# 01_2019_-_PLACA_LEDS_V1.net
KiCad netlist of a schematic drawn in EAGLE
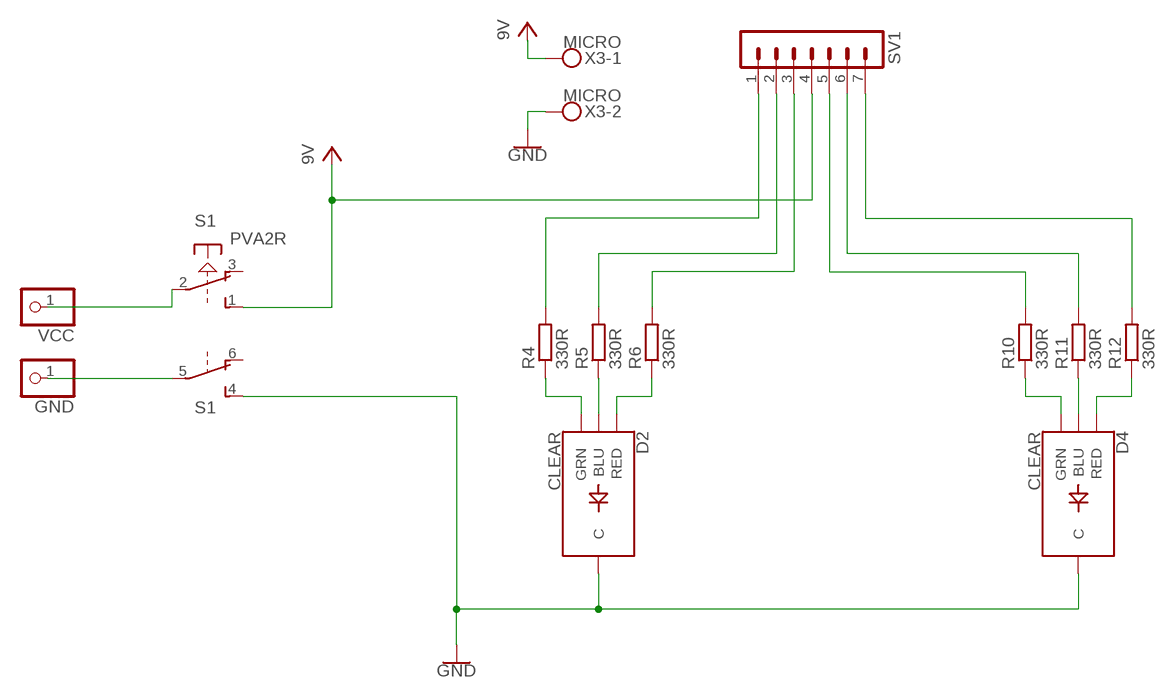
[diagram p0: schematic, sheet 1]

(export (version "E")
  (design (tool "Eeschema 10.0.6"))
  (components
    (comp (ref "D2")
      (value "CLEAR")
      (footprint "eagle-import:LED-RGB-THRU")
      (libsource (lib "eagle-import") (part "LED-RGB-CCCLEAR"))
    )
    (comp (ref "D4")
      (value "CLEAR")
      (footprint "eagle-import:LED-RGB-THRU")
      (libsource (lib "eagle-import") (part "LED-RGB-CCCLEAR"))
    )
    (comp (ref "GND")
      (value "PINHD-1X1")
      (footprint "eagle-import:1X01")
      (libsource (lib "eagle-import") (part "PINHD-1X1"))
    )
    (comp (ref "R4")
      (value "330R")
      (footprint "eagle-import:0204_7")
      (libsource (lib "eagle-import") (part "R-EU_0204/7"))
    )
    (comp (ref "R5")
      (value "330R")
      (footprint "eagle-import:0204_7")
      (libsource (lib "eagle-import") (part "R-EU_0204/7"))
    )
    (comp (ref "R6")
      (value "330R")
      (footprint "eagle-import:0204_7")
      (libsource (lib "eagle-import") (part "R-EU_0204/7"))
    )
    (comp (ref "R10")
      (value "330R")
      (footprint "eagle-import:0204_7")
      (libsource (lib "eagle-import") (part "R-EU_0204/7"))
    )
    (comp (ref "R11")
      (value "330R")
      (footprint "eagle-import:0204_7")
      (libsource (lib "eagle-import") (part "R-EU_0204/7"))
    )
    (comp (ref "R12")
      (value "330R")
      (footprint "eagle-import:0204_7")
      (libsource (lib "eagle-import") (part "R-EU_0204/7"))
    )
    (comp (ref "S1")
      (value "PVA2R")
      (footprint "eagle-import:PVA2R")
      (libsource (lib "eagle-import") (part "PVA2R"))
    )
    (comp (ref "SV1")
      (value "MA07-1")
      (footprint "eagle-import:MA07-1")
      (libsource (lib "eagle-import") (part "MA07-1"))
    )
    (comp (ref "VCC")
      (value "PINHD-1X1")
      (footprint "eagle-import:1X01")
      (libsource (lib "eagle-import") (part "PINHD-1X1"))
    )
    (comp (ref "X3")
      (value "MICRO")
      (footprint "eagle-import:MKDSN1,5_2-5,08")
      (libsource (lib "eagle-import") (part "MKDSN1,5/2-5,08"))
    )
  )
  (nets
    (net (code "1") (name "9V") (class "Default")
      (node (ref "S1") (pin "1") (pinfunction "S_1") (pintype "passive"))
      (node (ref "SV1") (pin "4") (pinfunction "4_4") (pintype "passive"))
      (node (ref "X3") (pin "1") (pinfunction "KL_1") (pintype "passive"))
    )
    (net (code "2") (name "GND") (class "Default")
      (node (ref "D2") (pin "2") (pinfunction "C_2") (pintype "bidirectional"))
      (node (ref "D4") (pin "2") (pinfunction "C_2") (pintype "bidirectional"))
      (node (ref "S1") (pin "4") (pinfunction "S_4") (pintype "passive"))
      (node (ref "X3") (pin "2") (pinfunction "KL_2") (pintype "passive"))
    )
    (net (code "3") (name "Net-(D2-BLU)") (class "Default")
      (node (ref "D2") (pin "4") (pinfunction "BLU_4") (pintype "bidirectional"))
      (node (ref "R5") (pin "1") (pinfunction "1_1") (pintype "passive"))
    )
    (net (code "4") (name "Net-(D2-GRN)") (class "Default")
      (node (ref "D2") (pin "3") (pinfunction "GRN_3") (pintype "bidirectional"))
      (node (ref "R4") (pin "1") (pinfunction "1_1") (pintype "passive"))
    )
    (net (code "5") (name "Net-(D2-RED)") (class "Default")
      (node (ref "D2") (pin "1") (pinfunction "RED_1") (pintype "bidirectional"))
      (node (ref "R6") (pin "1") (pinfunction "1_1") (pintype "passive"))
    )
    (net (code "6") (name "Net-(D4-BLU)") (class "Default")
      (node (ref "D4") (pin "4") (pinfunction "BLU_4") (pintype "bidirectional"))
      (node (ref "R11") (pin "1") (pinfunction "1_1") (pintype "passive"))
    )
    (net (code "7") (name "Net-(D4-GRN)") (class "Default")
      (node (ref "D4") (pin "3") (pinfunction "GRN_3") (pintype "bidirectional"))
      (node (ref "R10") (pin "1") (pinfunction "1_1") (pintype "passive"))
    )
    (net (code "8") (name "Net-(D4-RED)") (class "Default")
      (node (ref "D4") (pin "1") (pinfunction "RED_1") (pintype "bidirectional"))
      (node (ref "R12") (pin "1") (pinfunction "1_1") (pintype "passive"))
    )
    (net (code "9") (name "Net-(R4-Pad2)") (class "Default")
      (node (ref "R4") (pin "2") (pinfunction "2_2") (pintype "passive"))
      (node (ref "SV1") (pin "1") (pinfunction "1_1") (pintype "passive"))
    )
    (net (code "10") (name "Net-(R5-Pad2)") (class "Default")
      (node (ref "R5") (pin "2") (pinfunction "2_2") (pintype "passive"))
      (node (ref "SV1") (pin "2") (pinfunction "2_2") (pintype "passive"))
    )
    (net (code "11") (name "Net-(R6-Pad2)") (class "Default")
      (node (ref "R6") (pin "2") (pinfunction "2_2") (pintype "passive"))
      (node (ref "SV1") (pin "3") (pinfunction "3_3") (pintype "passive"))
    )
    (net (code "12") (name "Net-(R10-Pad2)") (class "Default")
      (node (ref "R10") (pin "2") (pinfunction "2_2") (pintype "passive"))
      (node (ref "SV1") (pin "5") (pinfunction "5_5") (pintype "passive"))
    )
    (net (code "13") (name "Net-(R11-Pad2)") (class "Default")
      (node (ref "R11") (pin "2") (pinfunction "2_2") (pintype "passive"))
      (node (ref "SV1") (pin "6") (pinfunction "6_6") (pintype "passive"))
    )
    (net (code "14") (name "Net-(R12-Pad2)") (class "Default")
      (node (ref "R12") (pin "2") (pinfunction "2_2") (pintype "passive"))
      (node (ref "SV1") (pin "7") (pinfunction "7_7") (pintype "passive"))
    )
    (net (code "15") (name "Net-(S1A-P)") (class "Default")
      (node (ref "S1") (pin "2") (pinfunction "P_2") (pintype "passive"))
      (node (ref "VCC") (pin "1") (pinfunction "1_1") (pintype "passive"))
    )
    (net (code "16") (name "Net-(S1B-P)") (class "Default")
      (node (ref "GND") (pin "1") (pinfunction "1_1") (pintype "passive"))
      (node (ref "S1") (pin "5") (pinfunction "P_5") (pintype "passive"))
    )
    (net (code "17") (name "unconnected-(S1A-O-Pad3)") (class "Default")
      (node (ref "S1") (pin "3") (pinfunction "O_3") (pintype "passive"))
    )
    (net (code "18") (name "unconnected-(S1B-O-Pad6)") (class "Default")
      (node (ref "S1") (pin "6") (pinfunction "O_6") (pintype "passive"))
    )
  )
)
